# connection_Sheet.net
KiCad netlist of a schematic drawn in Altium Designer
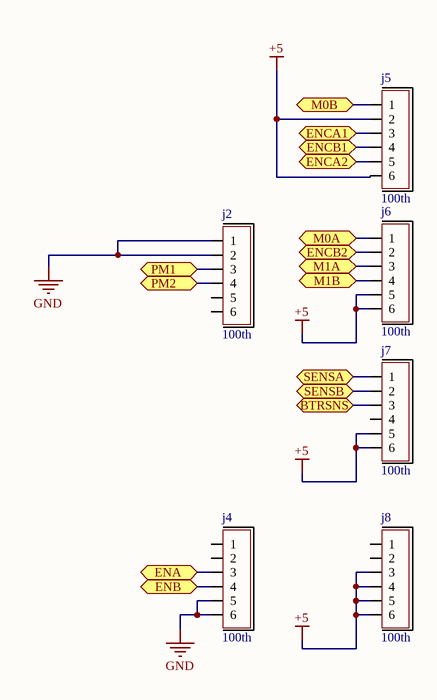
[diagram p0: connection_Sheet.SchDoc]

(export (version "E")
  (design (tool "Eeschema 10.0.6"))
  (components
    (comp (ref "j2")
      (value "100th")
      (footprint "pin6header")
      (libsource (lib "pin6header") (part "pin6header"))
    )
    (comp (ref "j4")
      (value "100th")
      (footprint "pin6header")
      (libsource (lib "pin6header") (part "pin6header"))
    )
    (comp (ref "j5")
      (value "100th")
      (footprint "pin6header")
      (libsource (lib "pin6header") (part "pin6header"))
    )
    (comp (ref "j6")
      (value "100th")
      (footprint "pin6header")
      (libsource (lib "pin6header") (part "pin6header"))
    )
    (comp (ref "j7")
      (value "100th")
      (footprint "pin6header")
      (libsource (lib "pin6header") (part "pin6header"))
    )
    (comp (ref "j8")
      (value "100th")
      (footprint "pin6header")
      (libsource (lib "pin6header") (part "pin6header"))
    )
  )
  (nets
    (net (code "1") (name "+5") (class "Default")
      (node (ref "j5") (pin "2") (pinfunction "2_2") (pintype "passive"))
      (node (ref "j5") (pin "6") (pinfunction "6_6") (pintype "passive"))
      (node (ref "j6") (pin "5") (pinfunction "5_5") (pintype "passive"))
      (node (ref "j6") (pin "6") (pinfunction "6_6") (pintype "passive"))
      (node (ref "j7") (pin "5") (pinfunction "5_5") (pintype "passive"))
      (node (ref "j7") (pin "6") (pinfunction "6_6") (pintype "passive"))
      (node (ref "j8") (pin "3") (pinfunction "3_3") (pintype "passive"))
      (node (ref "j8") (pin "4") (pinfunction "4_4") (pintype "passive"))
      (node (ref "j8") (pin "5") (pinfunction "5_5") (pintype "passive"))
      (node (ref "j8") (pin "6") (pinfunction "6_6") (pintype "passive"))
    )
    (net (code "2") (name "/BTRSNS") (class "Default")
      (node (ref "j7") (pin "3") (pinfunction "3_3") (pintype "passive"))
    )
    (net (code "3") (name "/ENA") (class "Default")
      (node (ref "j4") (pin "3") (pinfunction "3_3") (pintype "passive"))
    )
    (net (code "4") (name "/ENB") (class "Default")
      (node (ref "j4") (pin "4") (pinfunction "4_4") (pintype "passive"))
    )
    (net (code "5") (name "/ENCA1") (class "Default")
      (node (ref "j5") (pin "3") (pinfunction "3_3") (pintype "passive"))
    )
    (net (code "6") (name "/ENCA2") (class "Default")
      (node (ref "j5") (pin "5") (pinfunction "5_5") (pintype "passive"))
    )
    (net (code "7") (name "/ENCB1") (class "Default")
      (node (ref "j5") (pin "4") (pinfunction "4_4") (pintype "passive"))
    )
    (net (code "8") (name "/ENCB2") (class "Default")
      (node (ref "j6") (pin "2") (pinfunction "2_2") (pintype "passive"))
    )
    (net (code "9") (name "/M0A") (class "Default")
      (node (ref "j6") (pin "1") (pinfunction "1_1") (pintype "passive"))
    )
    (net (code "10") (name "/M0B") (class "Default")
      (node (ref "j5") (pin "1") (pinfunction "1_1") (pintype "passive"))
    )
    (net (code "11") (name "/M1A") (class "Default")
      (node (ref "j6") (pin "3") (pinfunction "3_3") (pintype "passive"))
    )
    (net (code "12") (name "/M1B") (class "Default")
      (node (ref "j6") (pin "4") (pinfunction "4_4") (pintype "passive"))
    )
    (net (code "13") (name "/PM1") (class "Default")
      (node (ref "j2") (pin "3") (pinfunction "3_3") (pintype "passive"))
    )
    (net (code "14") (name "/PM2") (class "Default")
      (node (ref "j2") (pin "4") (pinfunction "4_4") (pintype "passive"))
    )
    (net (code "15") (name "/SENSA") (class "Default")
      (node (ref "j7") (pin "1") (pinfunction "1_1") (pintype "passive"))
    )
    (net (code "16") (name "/SENSB") (class "Default")
      (node (ref "j7") (pin "2") (pinfunction "2_2") (pintype "passive"))
    )
    (net (code "17") (name "GND") (class "Default")
      (node (ref "j2") (pin "1") (pinfunction "1_1") (pintype "passive"))
      (node (ref "j2") (pin "2") (pinfunction "2_2") (pintype "passive"))
      (node (ref "j4") (pin "5") (pinfunction "5_5") (pintype "passive"))
      (node (ref "j4") (pin "6") (pinfunction "6_6") (pintype "passive"))
    )
    (net (code "18") (name "unconnected-(j2-Pad5)") (class "Default")
      (node (ref "j2") (pin "5") (pinfunction "5_5") (pintype "passive"))
    )
    (net (code "19") (name "unconnected-(j2-Pad6)") (class "Default")
      (node (ref "j2") (pin "6") (pinfunction "6_6") (pintype "passive"))
    )
    (net (code "20") (name "unconnected-(j4-Pad1)") (class "Default")
      (node (ref "j4") (pin "1") (pinfunction "1_1") (pintype "passive"))
    )
    (net (code "21") (name "unconnected-(j4-Pad2)") (class "Default")
      (node (ref "j4") (pin "2") (pinfunction "2_2") (pintype "passive"))
    )
    (net (code "22") (name "unconnected-(j7-Pad4)") (class "Default")
      (node (ref "j7") (pin "4") (pinfunction "4_4") (pintype "passive"))
    )
    (net (code "23") (name "unconnected-(j8-Pad1)") (class "Default")
      (node (ref "j8") (pin "1") (pinfunction "1_1") (pintype "passive"))
    )
    (net (code "24") (name "unconnected-(j8-Pad2)") (class "Default")
      (node (ref "j8") (pin "2") (pinfunction "2_2") (pintype "passive"))
    )
  )
)
